# TopSide.net
KiCad netlist of a schematic drawn in Altium Designer
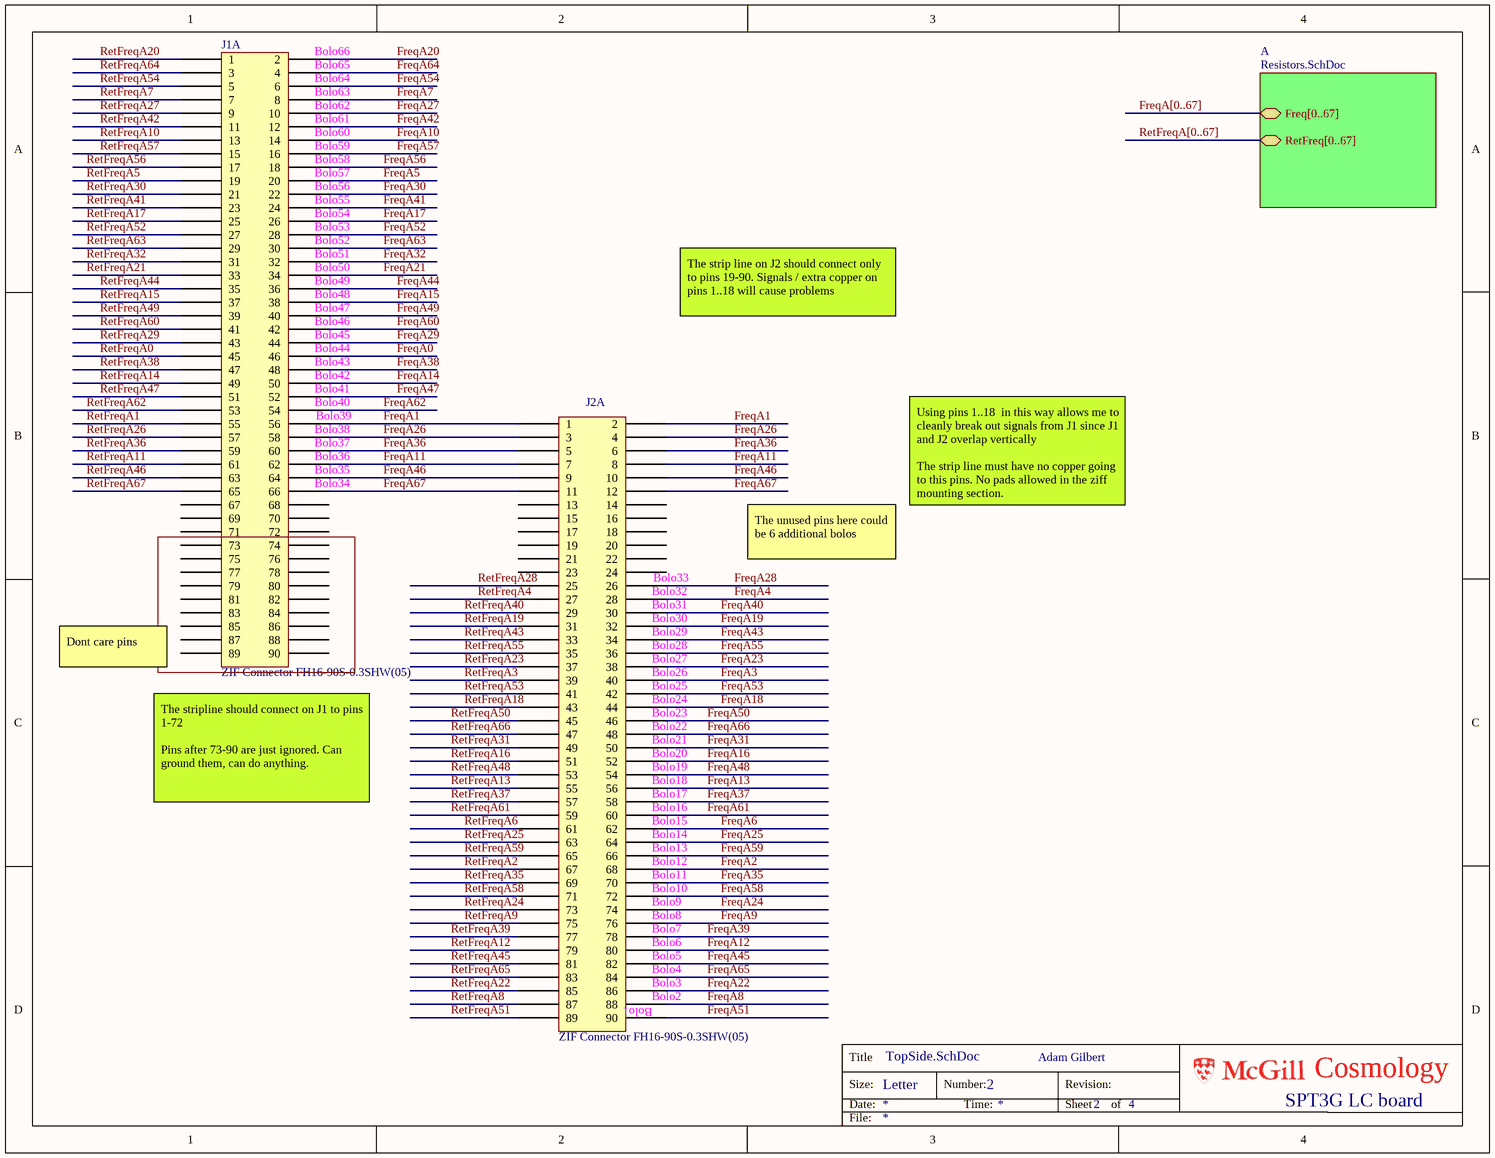
[diagram p0: TopSide.SchDoc]

(export (version "E")
  (design (tool "Eeschema 10.0.6"))
  (components
    (comp (ref "J1A")
      (value "ZIF Connector FH16-90S-0.3SHW(05)")
      (footprint "LCBoard_ZIFCon")
      (libsource (lib "SPT3G_LCBoard") (part "LCboard_FH16-90S-0.3SHW(05)"))
    )
    (comp (ref "J2A")
      (value "ZIF Connector FH16-90S-0.3SHW(05)")
      (footprint "LCBoard_ZIFCon")
      (libsource (lib "SPT3G_LCBoard") (part "LCboard_FH16-90S-0.3SHW(05)"))
    )
  )
  (nets
    (net (code "5") (name "/FreqA0") (class "Default")
      (node (ref "J1A") (pin "46") (pinfunction "46_46") (pintype "passive"))
    )
    (net (code "6") (name "/FreqA1") (class "Default")
      (node (ref "J1A") (pin "56") (pinfunction "56_56") (pintype "passive"))
      (node (ref "J2A") (pin "1") (pinfunction "1_1") (pintype "passive"))
      (node (ref "J2A") (pin "2") (pinfunction "2_2") (pintype "passive"))
    )
    (net (code "7") (name "/FreqA2") (class "Default")
      (node (ref "J2A") (pin "68") (pinfunction "68_68") (pintype "passive"))
    )
    (net (code "8") (name "/FreqA3") (class "Default")
      (node (ref "J2A") (pin "40") (pinfunction "40_40") (pintype "passive"))
    )
    (net (code "9") (name "/FreqA4") (class "Default")
      (node (ref "J2A") (pin "28") (pinfunction "28_28") (pintype "passive"))
    )
    (net (code "10") (name "/FreqA5") (class "Default")
      (node (ref "J1A") (pin "20") (pinfunction "20_20") (pintype "passive"))
    )
    (net (code "11") (name "/FreqA6") (class "Default")
      (node (ref "J2A") (pin "62") (pinfunction "62_62") (pintype "passive"))
    )
    (net (code "12") (name "/FreqA7") (class "Default")
      (node (ref "J1A") (pin "8") (pinfunction "8_8") (pintype "passive"))
    )
    (net (code "13") (name "/FreqA8") (class "Default")
      (node (ref "J2A") (pin "88") (pinfunction "88_88") (pintype "passive"))
    )
    (net (code "14") (name "/FreqA9") (class "Default")
      (node (ref "J2A") (pin "76") (pinfunction "76_76") (pintype "passive"))
    )
    (net (code "15") (name "/FreqA10") (class "Default")
      (node (ref "J1A") (pin "14") (pinfunction "14_14") (pintype "passive"))
    )
    (net (code "16") (name "/FreqA11") (class "Default")
      (node (ref "J1A") (pin "62") (pinfunction "62_62") (pintype "passive"))
      (node (ref "J2A") (pin "7") (pinfunction "7_7") (pintype "passive"))
      (node (ref "J2A") (pin "8") (pinfunction "8_8") (pintype "passive"))
    )
    (net (code "17") (name "/FreqA12") (class "Default")
      (node (ref "J2A") (pin "80") (pinfunction "80_80") (pintype "passive"))
    )
    (net (code "18") (name "/FreqA13") (class "Default")
      (node (ref "J2A") (pin "56") (pinfunction "56_56") (pintype "passive"))
    )
    (net (code "19") (name "/FreqA14") (class "Default")
      (node (ref "J1A") (pin "50") (pinfunction "50_50") (pintype "passive"))
    )
    (net (code "20") (name "/FreqA15") (class "Default")
      (node (ref "J1A") (pin "38") (pinfunction "38_38") (pintype "passive"))
    )
    (net (code "21") (name "/FreqA16") (class "Default")
      (node (ref "J2A") (pin "52") (pinfunction "52_52") (pintype "passive"))
    )
    (net (code "22") (name "/FreqA17") (class "Default")
      (node (ref "J1A") (pin "26") (pinfunction "26_26") (pintype "passive"))
    )
    (net (code "23") (name "/FreqA18") (class "Default")
      (node (ref "J2A") (pin "44") (pinfunction "44_44") (pintype "passive"))
    )
    (net (code "24") (name "/FreqA19") (class "Default")
      (node (ref "J2A") (pin "32") (pinfunction "32_32") (pintype "passive"))
    )
    (net (code "25") (name "/FreqA20") (class "Default")
      (node (ref "J1A") (pin "2") (pinfunction "2_2") (pintype "passive"))
    )
    (net (code "26") (name "/FreqA21") (class "Default")
      (node (ref "J1A") (pin "34") (pinfunction "34_34") (pintype "passive"))
    )
    (net (code "27") (name "/FreqA22") (class "Default")
      (node (ref "J2A") (pin "86") (pinfunction "86_86") (pintype "passive"))
    )
    (net (code "28") (name "/FreqA23") (class "Default")
      (node (ref "J2A") (pin "38") (pinfunction "38_38") (pintype "passive"))
    )
    (net (code "29") (name "/FreqA24") (class "Default")
      (node (ref "J2A") (pin "74") (pinfunction "74_74") (pintype "passive"))
    )
    (net (code "30") (name "/FreqA25") (class "Default")
      (node (ref "J2A") (pin "64") (pinfunction "64_64") (pintype "passive"))
    )
    (net (code "31") (name "/FreqA26") (class "Default")
      (node (ref "J1A") (pin "58") (pinfunction "58_58") (pintype "passive"))
      (node (ref "J2A") (pin "3") (pinfunction "3_3") (pintype "passive"))
      (node (ref "J2A") (pin "4") (pinfunction "4_4") (pintype "passive"))
    )
    (net (code "32") (name "/FreqA27") (class "Default")
      (node (ref "J1A") (pin "10") (pinfunction "10_10") (pintype "passive"))
    )
    (net (code "33") (name "/FreqA28") (class "Default")
      (node (ref "J2A") (pin "26") (pinfunction "26_26") (pintype "passive"))
    )
    (net (code "34") (name "/FreqA29") (class "Default")
      (node (ref "J1A") (pin "44") (pinfunction "44_44") (pintype "passive"))
    )
    (net (code "35") (name "/FreqA30") (class "Default")
      (node (ref "J1A") (pin "22") (pinfunction "22_22") (pintype "passive"))
    )
    (net (code "36") (name "/FreqA31") (class "Default")
      (node (ref "J2A") (pin "50") (pinfunction "50_50") (pintype "passive"))
    )
    (net (code "37") (name "/FreqA32") (class "Default")
      (node (ref "J1A") (pin "32") (pinfunction "32_32") (pintype "passive"))
    )
    (net (code "38") (name "/FreqA35") (class "Default")
      (node (ref "J2A") (pin "70") (pinfunction "70_70") (pintype "passive"))
    )
    (net (code "39") (name "/FreqA36") (class "Default")
      (node (ref "J1A") (pin "60") (pinfunction "60_60") (pintype "passive"))
      (node (ref "J2A") (pin "5") (pinfunction "5_5") (pintype "passive"))
      (node (ref "J2A") (pin "6") (pinfunction "6_6") (pintype "passive"))
    )
    (net (code "40") (name "/FreqA37") (class "Default")
      (node (ref "J2A") (pin "58") (pinfunction "58_58") (pintype "passive"))
    )
    (net (code "41") (name "/FreqA38") (class "Default")
      (node (ref "J1A") (pin "48") (pinfunction "48_48") (pintype "passive"))
    )
    (net (code "42") (name "/FreqA39") (class "Default")
      (node (ref "J2A") (pin "78") (pinfunction "78_78") (pintype "passive"))
    )
    (net (code "43") (name "/FreqA40") (class "Default")
      (node (ref "J2A") (pin "30") (pinfunction "30_30") (pintype "passive"))
    )
    (net (code "44") (name "/FreqA41") (class "Default")
      (node (ref "J1A") (pin "24") (pinfunction "24_24") (pintype "passive"))
    )
    (net (code "45") (name "/FreqA42") (class "Default")
      (node (ref "J1A") (pin "12") (pinfunction "12_12") (pintype "passive"))
    )
    (net (code "46") (name "/FreqA43") (class "Default")
      (node (ref "J2A") (pin "34") (pinfunction "34_34") (pintype "passive"))
    )
    (net (code "47") (name "/FreqA44") (class "Default")
      (node (ref "J1A") (pin "36") (pinfunction "36_36") (pintype "passive"))
    )
    (net (code "48") (name "/FreqA45") (class "Default")
      (node (ref "J2A") (pin "82") (pinfunction "82_82") (pintype "passive"))
    )
    (net (code "49") (name "/FreqA46") (class "Default")
      (node (ref "J1A") (pin "64") (pinfunction "64_64") (pintype "passive"))
      (node (ref "J2A") (pin "10") (pinfunction "10_10") (pintype "passive"))
      (node (ref "J2A") (pin "9") (pinfunction "9_9") (pintype "passive"))
    )
    (net (code "50") (name "/FreqA47") (class "Default")
      (node (ref "J1A") (pin "52") (pinfunction "52_52") (pintype "passive"))
    )
    (net (code "51") (name "/FreqA48") (class "Default")
      (node (ref "J2A") (pin "54") (pinfunction "54_54") (pintype "passive"))
    )
    (net (code "52") (name "/FreqA49") (class "Default")
      (node (ref "J1A") (pin "40") (pinfunction "40_40") (pintype "passive"))
    )
    (net (code "53") (name "/FreqA50") (class "Default")
      (node (ref "J2A") (pin "46") (pinfunction "46_46") (pintype "passive"))
    )
    (net (code "54") (name "/FreqA51") (class "Default")
      (node (ref "J2A") (pin "90") (pinfunction "90_90") (pintype "passive"))
    )
    (net (code "55") (name "/FreqA52") (class "Default")
      (node (ref "J1A") (pin "28") (pinfunction "28_28") (pintype "passive"))
    )
    (net (code "56") (name "/FreqA53") (class "Default")
      (node (ref "J2A") (pin "42") (pinfunction "42_42") (pintype "passive"))
    )
    (net (code "57") (name "/FreqA54") (class "Default")
      (node (ref "J1A") (pin "6") (pinfunction "6_6") (pintype "passive"))
    )
    (net (code "58") (name "/FreqA55") (class "Default")
      (node (ref "J2A") (pin "36") (pinfunction "36_36") (pintype "passive"))
    )
    (net (code "59") (name "/FreqA56") (class "Default")
      (node (ref "J1A") (pin "18") (pinfunction "18_18") (pintype "passive"))
    )
    (net (code "60") (name "/FreqA57") (class "Default")
      (node (ref "J1A") (pin "16") (pinfunction "16_16") (pintype "passive"))
    )
    (net (code "61") (name "/FreqA58") (class "Default")
      (node (ref "J2A") (pin "72") (pinfunction "72_72") (pintype "passive"))
    )
    (net (code "62") (name "/FreqA59") (class "Default")
      (node (ref "J2A") (pin "66") (pinfunction "66_66") (pintype "passive"))
    )
    (net (code "63") (name "/FreqA60") (class "Default")
      (node (ref "J1A") (pin "42") (pinfunction "42_42") (pintype "passive"))
    )
    (net (code "64") (name "/FreqA61") (class "Default")
      (node (ref "J2A") (pin "60") (pinfunction "60_60") (pintype "passive"))
    )
    (net (code "65") (name "/FreqA62") (class "Default")
      (node (ref "J1A") (pin "54") (pinfunction "54_54") (pintype "passive"))
    )
    (net (code "66") (name "/FreqA63") (class "Default")
      (node (ref "J1A") (pin "30") (pinfunction "30_30") (pintype "passive"))
    )
    (net (code "67") (name "/FreqA64") (class "Default")
      (node (ref "J1A") (pin "4") (pinfunction "4_4") (pintype "passive"))
    )
    (net (code "68") (name "/FreqA65") (class "Default")
      (node (ref "J2A") (pin "84") (pinfunction "84_84") (pintype "passive"))
    )
    (net (code "69") (name "/FreqA66") (class "Default")
      (node (ref "J2A") (pin "48") (pinfunction "48_48") (pintype "passive"))
    )
    (net (code "70") (name "/FreqA67") (class "Default")
      (node (ref "J1A") (pin "66") (pinfunction "66_66") (pintype "passive"))
      (node (ref "J2A") (pin "11") (pinfunction "11_11") (pintype "passive"))
      (node (ref "J2A") (pin "12") (pinfunction "12_12") (pintype "passive"))
    )
    (net (code "72") (name "/RetFreqA0") (class "Default")
      (node (ref "J1A") (pin "45") (pinfunction "45_45") (pintype "passive"))
    )
    (net (code "73") (name "/RetFreqA1") (class "Default")
      (node (ref "J1A") (pin "55") (pinfunction "55_55") (pintype "passive"))
    )
    (net (code "74") (name "/RetFreqA2") (class "Default")
      (node (ref "J2A") (pin "67") (pinfunction "67_67") (pintype "passive"))
    )
    (net (code "75") (name "/RetFreqA3") (class "Default")
      (node (ref "J2A") (pin "39") (pinfunction "39_39") (pintype "passive"))
    )
    (net (code "76") (name "/RetFreqA4") (class "Default")
      (node (ref "J2A") (pin "27") (pinfunction "27_27") (pintype "passive"))
    )
    (net (code "77") (name "/RetFreqA5") (class "Default")
      (node (ref "J1A") (pin "19") (pinfunction "19_19") (pintype "passive"))
    )
    (net (code "78") (name "/RetFreqA6") (class "Default")
      (node (ref "J2A") (pin "61") (pinfunction "61_61") (pintype "passive"))
    )
    (net (code "79") (name "/RetFreqA7") (class "Default")
      (node (ref "J1A") (pin "7") (pinfunction "7_7") (pintype "passive"))
    )
    (net (code "80") (name "/RetFreqA8") (class "Default")
      (node (ref "J2A") (pin "87") (pinfunction "87_87") (pintype "passive"))
    )
    (net (code "81") (name "/RetFreqA9") (class "Default")
      (node (ref "J2A") (pin "75") (pinfunction "75_75") (pintype "passive"))
    )
    (net (code "82") (name "/RetFreqA10") (class "Default")
      (node (ref "J1A") (pin "13") (pinfunction "13_13") (pintype "passive"))
    )
    (net (code "83") (name "/RetFreqA11") (class "Default")
      (node (ref "J1A") (pin "61") (pinfunction "61_61") (pintype "passive"))
    )
    (net (code "84") (name "/RetFreqA12") (class "Default")
      (node (ref "J2A") (pin "79") (pinfunction "79_79") (pintype "passive"))
    )
    (net (code "85") (name "/RetFreqA13") (class "Default")
      (node (ref "J2A") (pin "55") (pinfunction "55_55") (pintype "passive"))
    )
    (net (code "86") (name "/RetFreqA14") (class "Default")
      (node (ref "J1A") (pin "49") (pinfunction "49_49") (pintype "passive"))
    )
    (net (code "87") (name "/RetFreqA15") (class "Default")
      (node (ref "J1A") (pin "37") (pinfunction "37_37") (pintype "passive"))
    )
    (net (code "88") (name "/RetFreqA16") (class "Default")
      (node (ref "J2A") (pin "51") (pinfunction "51_51") (pintype "passive"))
    )
    (net (code "89") (name "/RetFreqA17") (class "Default")
      (node (ref "J1A") (pin "25") (pinfunction "25_25") (pintype "passive"))
    )
    (net (code "90") (name "/RetFreqA18") (class "Default")
      (node (ref "J2A") (pin "43") (pinfunction "43_43") (pintype "passive"))
    )
    (net (code "91") (name "/RetFreqA19") (class "Default")
      (node (ref "J2A") (pin "31") (pinfunction "31_31") (pintype "passive"))
    )
    (net (code "92") (name "/RetFreqA20") (class "Default")
      (node (ref "J1A") (pin "1") (pinfunction "1_1") (pintype "passive"))
    )
    (net (code "93") (name "/RetFreqA21") (class "Default")
      (node (ref "J1A") (pin "33") (pinfunction "33_33") (pintype "passive"))
    )
    (net (code "94") (name "/RetFreqA22") (class "Default")
      (node (ref "J2A") (pin "85") (pinfunction "85_85") (pintype "passive"))
    )
    (net (code "95") (name "/RetFreqA23") (class "Default")
      (node (ref "J2A") (pin "37") (pinfunction "37_37") (pintype "passive"))
    )
    (net (code "96") (name "/RetFreqA24") (class "Default")
      (node (ref "J2A") (pin "73") (pinfunction "73_73") (pintype "passive"))
    )
    (net (code "97") (name "/RetFreqA25") (class "Default")
      (node (ref "J2A") (pin "63") (pinfunction "63_63") (pintype "passive"))
    )
    (net (code "98") (name "/RetFreqA26") (class "Default")
      (node (ref "J1A") (pin "57") (pinfunction "57_57") (pintype "passive"))
    )
    (net (code "99") (name "/RetFreqA27") (class "Default")
      (node (ref "J1A") (pin "9") (pinfunction "9_9") (pintype "passive"))
    )
    (net (code "100") (name "/RetFreqA28") (class "Default")
      (node (ref "J2A") (pin "25") (pinfunction "25_25") (pintype "passive"))
    )
    (net (code "101") (name "/RetFreqA29") (class "Default")
      (node (ref "J1A") (pin "43") (pinfunction "43_43") (pintype "passive"))
    )
    (net (code "102") (name "/RetFreqA30") (class "Default")
      (node (ref "J1A") (pin "21") (pinfunction "21_21") (pintype "passive"))
    )
    (net (code "103") (name "/RetFreqA31") (class "Default")
      (node (ref "J2A") (pin "49") (pinfunction "49_49") (pintype "passive"))
    )
    (net (code "104") (name "/RetFreqA32") (class "Default")
      (node (ref "J1A") (pin "31") (pinfunction "31_31") (pintype "passive"))
    )
    (net (code "105") (name "/RetFreqA35") (class "Default")
      (node (ref "J2A") (pin "69") (pinfunction "69_69") (pintype "passive"))
    )
    (net (code "106") (name "/RetFreqA36") (class "Default")
      (node (ref "J1A") (pin "59") (pinfunction "59_59") (pintype "passive"))
    )
    (net (code "107") (name "/RetFreqA37") (class "Default")
      (node (ref "J2A") (pin "57") (pinfunction "57_57") (pintype "passive"))
    )
    (net (code "108") (name "/RetFreqA38") (class "Default")
      (node (ref "J1A") (pin "47") (pinfunction "47_47") (pintype "passive"))
    )
    (net (code "109") (name "/RetFreqA39") (class "Default")
      (node (ref "J2A") (pin "77") (pinfunction "77_77") (pintype "passive"))
    )
    (net (code "110") (name "/RetFreqA40") (class "Default")
      (node (ref "J2A") (pin "29") (pinfunction "29_29") (pintype "passive"))
    )
    (net (code "111") (name "/RetFreqA41") (class "Default")
      (node (ref "J1A") (pin "23") (pinfunction "23_23") (pintype "passive"))
    )
    (net (code "112") (name "/RetFreqA42") (class "Default")
      (node (ref "J1A") (pin "11") (pinfunction "11_11") (pintype "passive"))
    )
    (net (code "113") (name "/RetFreqA43") (class "Default")
      (node (ref "J2A") (pin "33") (pinfunction "33_33") (pintype "passive"))
    )
    (net (code "114") (name "/RetFreqA44") (class "Default")
      (node (ref "J1A") (pin "35") (pinfunction "35_35") (pintype "passive"))
    )
    (net (code "115") (name "/RetFreqA45") (class "Default")
      (node (ref "J2A") (pin "81") (pinfunction "81_81") (pintype "passive"))
    )
    (net (code "116") (name "/RetFreqA46") (class "Default")
      (node (ref "J1A") (pin "63") (pinfunction "63_63") (pintype "passive"))
    )
    (net (code "117") (name "/RetFreqA47") (class "Default")
      (node (ref "J1A") (pin "51") (pinfunction "51_51") (pintype "passive"))
    )
    (net (code "118") (name "/RetFreqA48") (class "Default")
      (node (ref "J2A") (pin "53") (pinfunction "53_53") (pintype "passive"))
    )
    (net (code "119") (name "/RetFreqA49") (class "Default")
      (node (ref "J1A") (pin "39") (pinfunction "39_39") (pintype "passive"))
    )
    (net (code "120") (name "/RetFreqA50") (class "Default")
      (node (ref "J2A") (pin "45") (pinfunction "45_45") (pintype "passive"))
    )
    (net (code "121") (name "/RetFreqA51") (class "Default")
      (node (ref "J2A") (pin "89") (pinfunction "89_89") (pintype "passive"))
    )
    (net (code "122") (name "/RetFreqA52") (class "Default")
      (node (ref "J1A") (pin "27") (pinfunction "27_27") (pintype "passive"))
    )
    (net (code "123") (name "/RetFreqA53") (class "Default")
      (node (ref "J2A") (pin "41") (pinfunction "41_41") (pintype "passive"))
    )
    (net (code "124") (name "/RetFreqA54") (class "Default")
      (node (ref "J1A") (pin "5") (pinfunction "5_5") (pintype "passive"))
    )
    (net (code "125") (name "/RetFreqA55") (class "Default")
      (node (ref "J2A") (pin "35") (pinfunction "35_35") (pintype "passive"))
    )
    (net (code "126") (name "/RetFreqA56") (class "Default")
      (node (ref "J1A") (pin "17") (pinfunction "17_17") (pintype "passive"))
    )
    (net (code "127") (name "/RetFreqA57") (class "Default")
      (node (ref "J1A") (pin "15") (pinfunction "15_15") (pintype "passive"))
    )
    (net (code "128") (name "/RetFreqA58") (class "Default")
      (node (ref "J2A") (pin "71") (pinfunction "71_71") (pintype "passive"))
    )
    (net (code "129") (name "/RetFreqA59") (class "Default")
      (node (ref "J2A") (pin "65") (pinfunction "65_65") (pintype "passive"))
    )
    (net (code "130") (name "/RetFreqA60") (class "Default")
      (node (ref "J1A") (pin "41") (pinfunction "41_41") (pintype "passive"))
    )
    (net (code "131") (name "/RetFreqA61") (class "Default")
      (node (ref "J2A") (pin "59") (pinfunction "59_59") (pintype "passive"))
    )
    (net (code "132") (name "/RetFreqA62") (class "Default")
      (node (ref "J1A") (pin "53") (pinfunction "53_53") (pintype "passive"))
    )
    (net (code "133") (name "/RetFreqA63") (class "Default")
      (node (ref "J1A") (pin "29") (pinfunction "29_29") (pintype "passive"))
    )
    (net (code "134") (name "/RetFreqA64") (class "Default")
      (node (ref "J1A") (pin "3") (pinfunction "3_3") (pintype "passive"))
    )
    (net (code "135") (name "/RetFreqA65") (class "Default")
      (node (ref "J2A") (pin "83") (pinfunction "83_83") (pintype "passive"))
    )
    (net (code "136") (name "/RetFreqA66") (class "Default")
      (node (ref "J2A") (pin "47") (pinfunction "47_47") (pintype "passive"))
    )
    (net (code "137") (name "/RetFreqA67") (class "Default")
      (node (ref "J1A") (pin "65") (pinfunction "65_65") (pintype "passive"))
    )
    (net (code "139") (name "unconnected-(J1A-Pad67)") (class "Default")
      (node (ref "J1A") (pin "67") (pinfunction "67_67") (pintype "passive"))
    )
    (net (code "140") (name "unconnected-(J1A-Pad68)") (class "Default")
      (node (ref "J1A") (pin "68") (pinfunction "68_68") (pintype "passive"))
    )
    (net (code "141") (name "unconnected-(J1A-Pad69)") (class "Default")
      (node (ref "J1A") (pin "69") (pinfunction "69_69") (pintype "passive"))
    )
    (net (code "142") (name "unconnected-(J1A-Pad70)") (class "Default")
      (node (ref "J1A") (pin "70") (pinfunction "70_70") (pintype "passive"))
    )
    (net (code "143") (name "unconnected-(J1A-Pad71)") (class "Default")
      (node (ref "J1A") (pin "71") (pinfunction "71_71") (pintype "passive"))
    )
    (net (code "144") (name "unconnected-(J1A-Pad72)") (class "Default")
      (node (ref "J1A") (pin "72") (pinfunction "72_72") (pintype "passive"))
    )
    (net (code "145") (name "unconnected-(J1A-Pad73)") (class "Default")
      (node (ref "J1A") (pin "73") (pinfunction "73_73") (pintype "passive"))
    )
    (net (code "146") (name "unconnected-(J1A-Pad74)") (class "Default")
      (node (ref "J1A") (pin "74") (pinfunction "74_74") (pintype "passive"))
    )
    (net (code "147") (name "unconnected-(J1A-Pad75)") (class "Default")
      (node (ref "J1A") (pin "75") (pinfunction "75_75") (pintype "passive"))
    )
    (net (code "148") (name "unconnected-(J1A-Pad76)") (class "Default")
      (node (ref "J1A") (pin "76") (pinfunction "76_76") (pintype "passive"))
    )
    (net (code "149") (name "unconnected-(J1A-Pad77)") (class "Default")
      (node (ref "J1A") (pin "77") (pinfunction "77_77") (pintype "passive"))
    )
    (net (code "150") (name "unconnected-(J1A-Pad78)") (class "Default")
      (node (ref "J1A") (pin "78") (pinfunction "78_78") (pintype "passive"))
    )
    (net (code "151") (name "unconnected-(J1A-Pad79)") (class "Default")
      (node (ref "J1A") (pin "79") (pinfunction "79_79") (pintype "passive"))
    )
    (net (code "152") (name "unconnected-(J1A-Pad80)") (class "Default")
      (node (ref "J1A") (pin "80") (pinfunction "80_80") (pintype "passive"))
    )
    (net (code "153") (name "unconnected-(J1A-Pad81)") (class "Default")
      (node (ref "J1A") (pin "81") (pinfunction "81_81") (pintype "passive"))
    )
    (net (code "154") (name "unconnected-(J1A-Pad82)") (class "Default")
      (node (ref "J1A") (pin "82") (pinfunction "82_82") (pintype "passive"))
    )
    (net (code "155") (name "unconnected-(J1A-Pad83)") (class "Default")
      (node (ref "J1A") (pin "83") (pinfunction "83_83") (pintype "passive"))
    )
    (net (code "156") (name "unconnected-(J1A-Pad84)") (class "Default")
      (node (ref "J1A") (pin "84") (pinfunction "84_84") (pintype "passive"))
    )
    (net (code "157") (name "unconnected-(J1A-Pad85)") (class "Default")
      (node (ref "J1A") (pin "85") (pinfunction "85_85") (pintype "passive"))
    )
    (net (code "158") (name "unconnected-(J1A-Pad86)") (class "Default")
      (node (ref "J1A") (pin "86") (pinfunction "86_86") (pintype "passive"))
    )
    (net (code "159") (name "unconnected-(J1A-Pad87)") (class "Default")
      (node (ref "J1A") (pin "87") (pinfunction "87_87") (pintype "passive"))
    )
    (net (code "160") (name "unconnected-(J1A-Pad88)") (class "Default")
      (node (ref "J1A") (pin "88") (pinfunction "88_88") (pintype "passive"))
    )
    (net (code "161") (name "unconnected-(J1A-Pad89)") (class "Default")
      (node (ref "J1A") (pin "89") (pinfunction "89_89") (pintype "passive"))
    )
    (net (code "162") (name "unconnected-(J1A-Pad90)") (class "Default")
      (node (ref "J1A") (pin "90") (pinfunction "90_90") (pintype "passive"))
    )
    (net (code "163") (name "unconnected-(J2A-Pad13)") (class "Default")
      (node (ref "J2A") (pin "13") (pinfunction "13_13") (pintype "passive"))
    )
    (net (code "164") (name "unconnected-(J2A-Pad14)") (class "Default")
      (node (ref "J2A") (pin "14") (pinfunction "14_14") (pintype "passive"))
    )
    (net (code "165") (name "unconnected-(J2A-Pad15)") (class "Default")
      (node (ref "J2A") (pin "15") (pinfunction "15_15") (pintype "passive"))
    )
    (net (code "166") (name "unconnected-(J2A-Pad16)") (class "Default")
      (node (ref "J2A") (pin "16") (pinfunction "16_16") (pintype "passive"))
    )
    (net (code "167") (name "unconnected-(J2A-Pad17)") (class "Default")
      (node (ref "J2A") (pin "17") (pinfunction "17_17") (pintype "passive"))
    )
    (net (code "168") (name "unconnected-(J2A-Pad18)") (class "Default")
      (node (ref "J2A") (pin "18") (pinfunction "18_18") (pintype "passive"))
    )
    (net (code "169") (name "unconnected-(J2A-Pad19)") (class "Default")
      (node (ref "J2A") (pin "19") (pinfunction "19_19") (pintype "passive"))
    )
    (net (code "170") (name "unconnected-(J2A-Pad20)") (class "Default")
      (node (ref "J2A") (pin "20") (pinfunction "20_20") (pintype "passive"))
    )
    (net (code "171") (name "unconnected-(J2A-Pad21)") (class "Default")
      (node (ref "J2A") (pin "21") (pinfunction "21_21") (pintype "passive"))
    )
    (net (code "172") (name "unconnected-(J2A-Pad22)") (class "Default")
      (node (ref "J2A") (pin "22") (pinfunction "22_22") (pintype "passive"))
    )
    (net (code "173") (name "unconnected-(J2A-Pad23)") (class "Default")
      (node (ref "J2A") (pin "23") (pinfunction "23_23") (pintype "passive"))
    )
    (net (code "174") (name "unconnected-(J2A-Pad24)") (class "Default")
      (node (ref "J2A") (pin "24") (pinfunction "24_24") (pintype "passive"))
    )
  )
)
